# BMS_AFE_-_Communications.net
KiCad netlist of a schematic drawn in Altium Designer
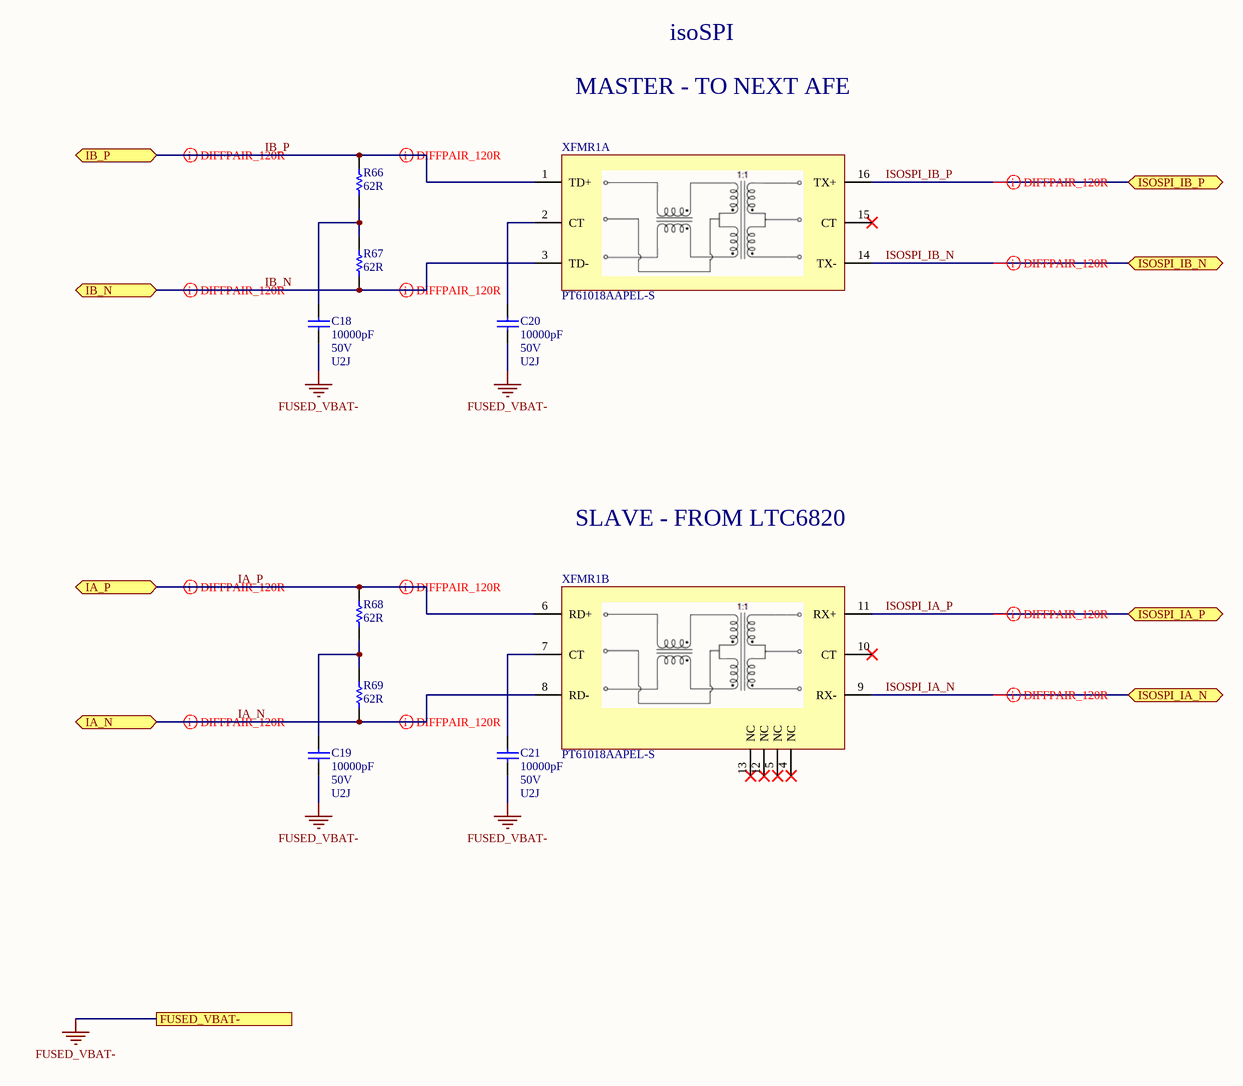
[diagram p0: BMS AFE - Communications.SchDoc]

(export (version "E")
  (design (tool "Eeschema 10.0.6"))
  (components
    (comp (ref "C18")
      (value "CAP CER 10nF 50V 5% X7R 0603")
      (footprint "CAP, 0603")
      (description "10000pF ±5% 50V Ceramic Capacitor U2J 0603 (1608 Metric)")
      (fields
        (field (name "TOLERANCE") "±5%")
        (field (name "CAPACITANCE") "10000pF")
        (field (name "VOLTAGE") "50V")
        (field (name "TEMPERATURE COEFFICIENT") "U2J")
      )
      (libsource (lib "Schematic Diagrams") (part "CAP CER 10nF 50V 5% X7R 0603"))
    )
    (comp (ref "C19")
      (value "CAP CER 10nF 50V 5% X7R 0603")
      (footprint "CAP, 0603")
      (description "10000pF ±5% 50V Ceramic Capacitor U2J 0603 (1608 Metric)")
      (fields
        (field (name "TOLERANCE") "±5%")
        (field (name "CAPACITANCE") "10000pF")
        (field (name "VOLTAGE") "50V")
        (field (name "TEMPERATURE COEFFICIENT") "U2J")
      )
      (libsource (lib "Schematic Diagrams") (part "CAP CER 10nF 50V 5% X7R 0603"))
    )
    (comp (ref "C20")
      (value "CAP CER 10nF 50V 5% X7R 0603")
      (footprint "CAP, 0603")
      (description "10000pF ±5% 50V Ceramic Capacitor U2J 0603 (1608 Metric)")
      (fields
        (field (name "TOLERANCE") "±5%")
        (field (name "CAPACITANCE") "10000pF")
        (field (name "VOLTAGE") "50V")
        (field (name "TEMPERATURE COEFFICIENT") "U2J")
      )
      (libsource (lib "Schematic Diagrams") (part "CAP CER 10nF 50V 5% X7R 0603"))
    )
    (comp (ref "C21")
      (value "CAP CER 10nF 50V 5% X7R 0603")
      (footprint "CAP, 0603")
      (description "10000pF ±5% 50V Ceramic Capacitor U2J 0603 (1608 Metric)")
      (fields
        (field (name "TOLERANCE") "±5%")
        (field (name "CAPACITANCE") "10000pF")
        (field (name "VOLTAGE") "50V")
        (field (name "TEMPERATURE COEFFICIENT") "U2J")
      )
      (libsource (lib "Schematic Diagrams") (part "CAP CER 10nF 50V 5% X7R 0603"))
    )
    (comp (ref "R66")
      (value "62R")
      (footprint "RES, 0603")
      (description "62 Ohms ±0.1% 0.1W, 1/10W Chip Resistor 0603 (1608 Metric) Automotive AEC-Q200 Thin Film")
      (fields
        (field (name "MANUFACTURER") "Panasonic Electronic Components")
        (field (name "MANUFACTURER PART NUMBER") "ERA-3AEB620V")
      )
      (libsource (lib "Schematic Diagrams") (part "RES 62 OHM 0.1% 1/10W 0603"))
    )
    (comp (ref "R67")
      (value "62R")
      (footprint "RES, 0603")
      (description "62 Ohms ±0.1% 0.1W, 1/10W Chip Resistor 0603 (1608 Metric) Automotive AEC-Q200 Thin Film")
      (fields
        (field (name "MANUFACTURER") "Panasonic Electronic Components")
        (field (name "MANUFACTURER PART NUMBER") "ERA-3AEB620V")
      )
      (libsource (lib "Schematic Diagrams") (part "RES 62 OHM 0.1% 1/10W 0603"))
    )
    (comp (ref "R68")
      (value "62R")
      (footprint "RES, 0603")
      (description "62 Ohms ±0.1% 0.1W, 1/10W Chip Resistor 0603 (1608 Metric) Automotive AEC-Q200 Thin Film")
      (fields
        (field (name "MANUFACTURER") "Panasonic Electronic Components")
        (field (name "MANUFACTURER PART NUMBER") "ERA-3AEB620V")
      )
      (libsource (lib "Schematic Diagrams") (part "RES 62 OHM 0.1% 1/10W 0603"))
    )
    (comp (ref "R69")
      (value "62R")
      (footprint "RES, 0603")
      (description "62 Ohms ±0.1% 0.1W, 1/10W Chip Resistor 0603 (1608 Metric) Automotive AEC-Q200 Thin Film")
      (fields
        (field (name "MANUFACTURER") "Panasonic Electronic Components")
        (field (name "MANUFACTURER PART NUMBER") "ERA-3AEB620V")
      )
      (libsource (lib "Schematic Diagrams") (part "RES 62 OHM 0.1% 1/10W 0603"))
    )
    (comp (ref "XFMR1")
      (value "IC PULSE XFMR 1CT:1CT 350UH SMD")
      (footprint "IC, PULSE XFMR 1CT:1CT 350UH SMD")
      (description "PULSE XFMR 1CT:1CT 350UH SMD")
      (fields (field (name "MANUFACTURER") "Bourns Inc.") (field (name "MFG_PN") "PT61018AAPEL-S"))
      (libsource (lib "Schematic Diagrams") (part "IC PULSE XFMR 1CT{colon}1CT 350UH SMD"))
    )
  )
  (nets
    (net (code "1") (name "/IA_N") (class "Default")
      (node (ref "R69") (pin "2") (pinfunction "2_2") (pintype "passive"))
      (node (ref "XFMR1") (pin "8") (pinfunction "RD-_8") (pintype "passive"))
    )
    (net (code "2") (name "/IA_P") (class "Default")
      (node (ref "R68") (pin "1") (pinfunction "1_1") (pintype "passive"))
      (node (ref "XFMR1") (pin "6") (pinfunction "RD+_6") (pintype "passive"))
    )
    (net (code "3") (name "/IB_N") (class "Default")
      (node (ref "R67") (pin "2") (pinfunction "2_2") (pintype "passive"))
      (node (ref "XFMR1") (pin "3") (pinfunction "TD-_3") (pintype "passive"))
    )
    (net (code "4") (name "/IB_P") (class "Default")
      (node (ref "R66") (pin "1") (pinfunction "1_1") (pintype "passive"))
      (node (ref "XFMR1") (pin "1") (pinfunction "TD+_1") (pintype "passive"))
    )
    (net (code "5") (name "/ISOSPI_IA_N") (class "Default")
      (node (ref "XFMR1") (pin "9") (pinfunction "RX-_9") (pintype "passive"))
    )
    (net (code "6") (name "/ISOSPI_IA_P") (class "Default")
      (node (ref "XFMR1") (pin "11") (pinfunction "RX+_11") (pintype "passive"))
    )
    (net (code "7") (name "/ISOSPI_IB_N") (class "Default")
      (node (ref "XFMR1") (pin "14") (pinfunction "TX-_14") (pintype "passive"))
    )
    (net (code "8") (name "/ISOSPI_IB_P") (class "Default")
      (node (ref "XFMR1") (pin "16") (pinfunction "TX+_16") (pintype "passive"))
    )
    (net (code "9") (name "FUSED_VBAT-") (class "Default")
      (node (ref "C18") (pin "2") (pinfunction "2_2") (pintype "passive"))
      (node (ref "C19") (pin "2") (pinfunction "2_2") (pintype "passive"))
      (node (ref "C20") (pin "2") (pinfunction "2_2") (pintype "passive"))
      (node (ref "C21") (pin "2") (pinfunction "2_2") (pintype "passive"))
    )
    (net (code "10") (name "Net-(C18-Pad1)") (class "Default")
      (node (ref "C18") (pin "1") (pinfunction "1_1") (pintype "passive"))
      (node (ref "R66") (pin "2") (pinfunction "2_2") (pintype "passive"))
      (node (ref "R67") (pin "1") (pinfunction "1_1") (pintype "passive"))
    )
    (net (code "11") (name "Net-(C19-Pad1)") (class "Default")
      (node (ref "C19") (pin "1") (pinfunction "1_1") (pintype "passive"))
      (node (ref "R68") (pin "2") (pinfunction "2_2") (pintype "passive"))
      (node (ref "R69") (pin "1") (pinfunction "1_1") (pintype "passive"))
    )
    (net (code "12") (name "Net-(C20-Pad1)") (class "Default")
      (node (ref "C20") (pin "1") (pinfunction "1_1") (pintype "passive"))
      (node (ref "XFMR1") (pin "2") (pinfunction "CT_2") (pintype "passive"))
    )
    (net (code "13") (name "Net-(C21-Pad1)") (class "Default")
      (node (ref "C21") (pin "1") (pinfunction "1_1") (pintype "passive"))
      (node (ref "XFMR1") (pin "7") (pinfunction "CT_7") (pintype "passive"))
    )
    (net (code "14") (name "unconnected-(XFMR1A-CT-Pad15)") (class "Default")
      (node (ref "XFMR1") (pin "15") (pinfunction "CT_15") (pintype "passive+no_connect"))
    )
    (net (code "15") (name "unconnected-(XFMR1B-CT-Pad10)") (class "Default")
      (node (ref "XFMR1") (pin "10") (pinfunction "CT_10") (pintype "passive+no_connect"))
    )
    (net (code "16") (name "unconnected-(XFMR1B-NC-Pad4)") (class "Default")
      (node (ref "XFMR1") (pin "4") (pinfunction "NC_4") (pintype "passive+no_connect"))
    )
    (net (code "17") (name "unconnected-(XFMR1B-NC-Pad5)") (class "Default")
      (node (ref "XFMR1") (pin "5") (pinfunction "NC_5") (pintype "passive+no_connect"))
    )
    (net (code "18") (name "unconnected-(XFMR1B-NC-Pad12)") (class "Default")
      (node (ref "XFMR1") (pin "12") (pinfunction "NC_12") (pintype "passive+no_connect"))
    )
    (net (code "19") (name "unconnected-(XFMR1B-NC-Pad13)") (class "Default")
      (node (ref "XFMR1") (pin "13") (pinfunction "NC_13") (pintype "passive+no_connect"))
    )
  )
)
